# SCH_RT1064_2024-05-07.net
KiCad netlist of a schematic drawn in EasyEDA
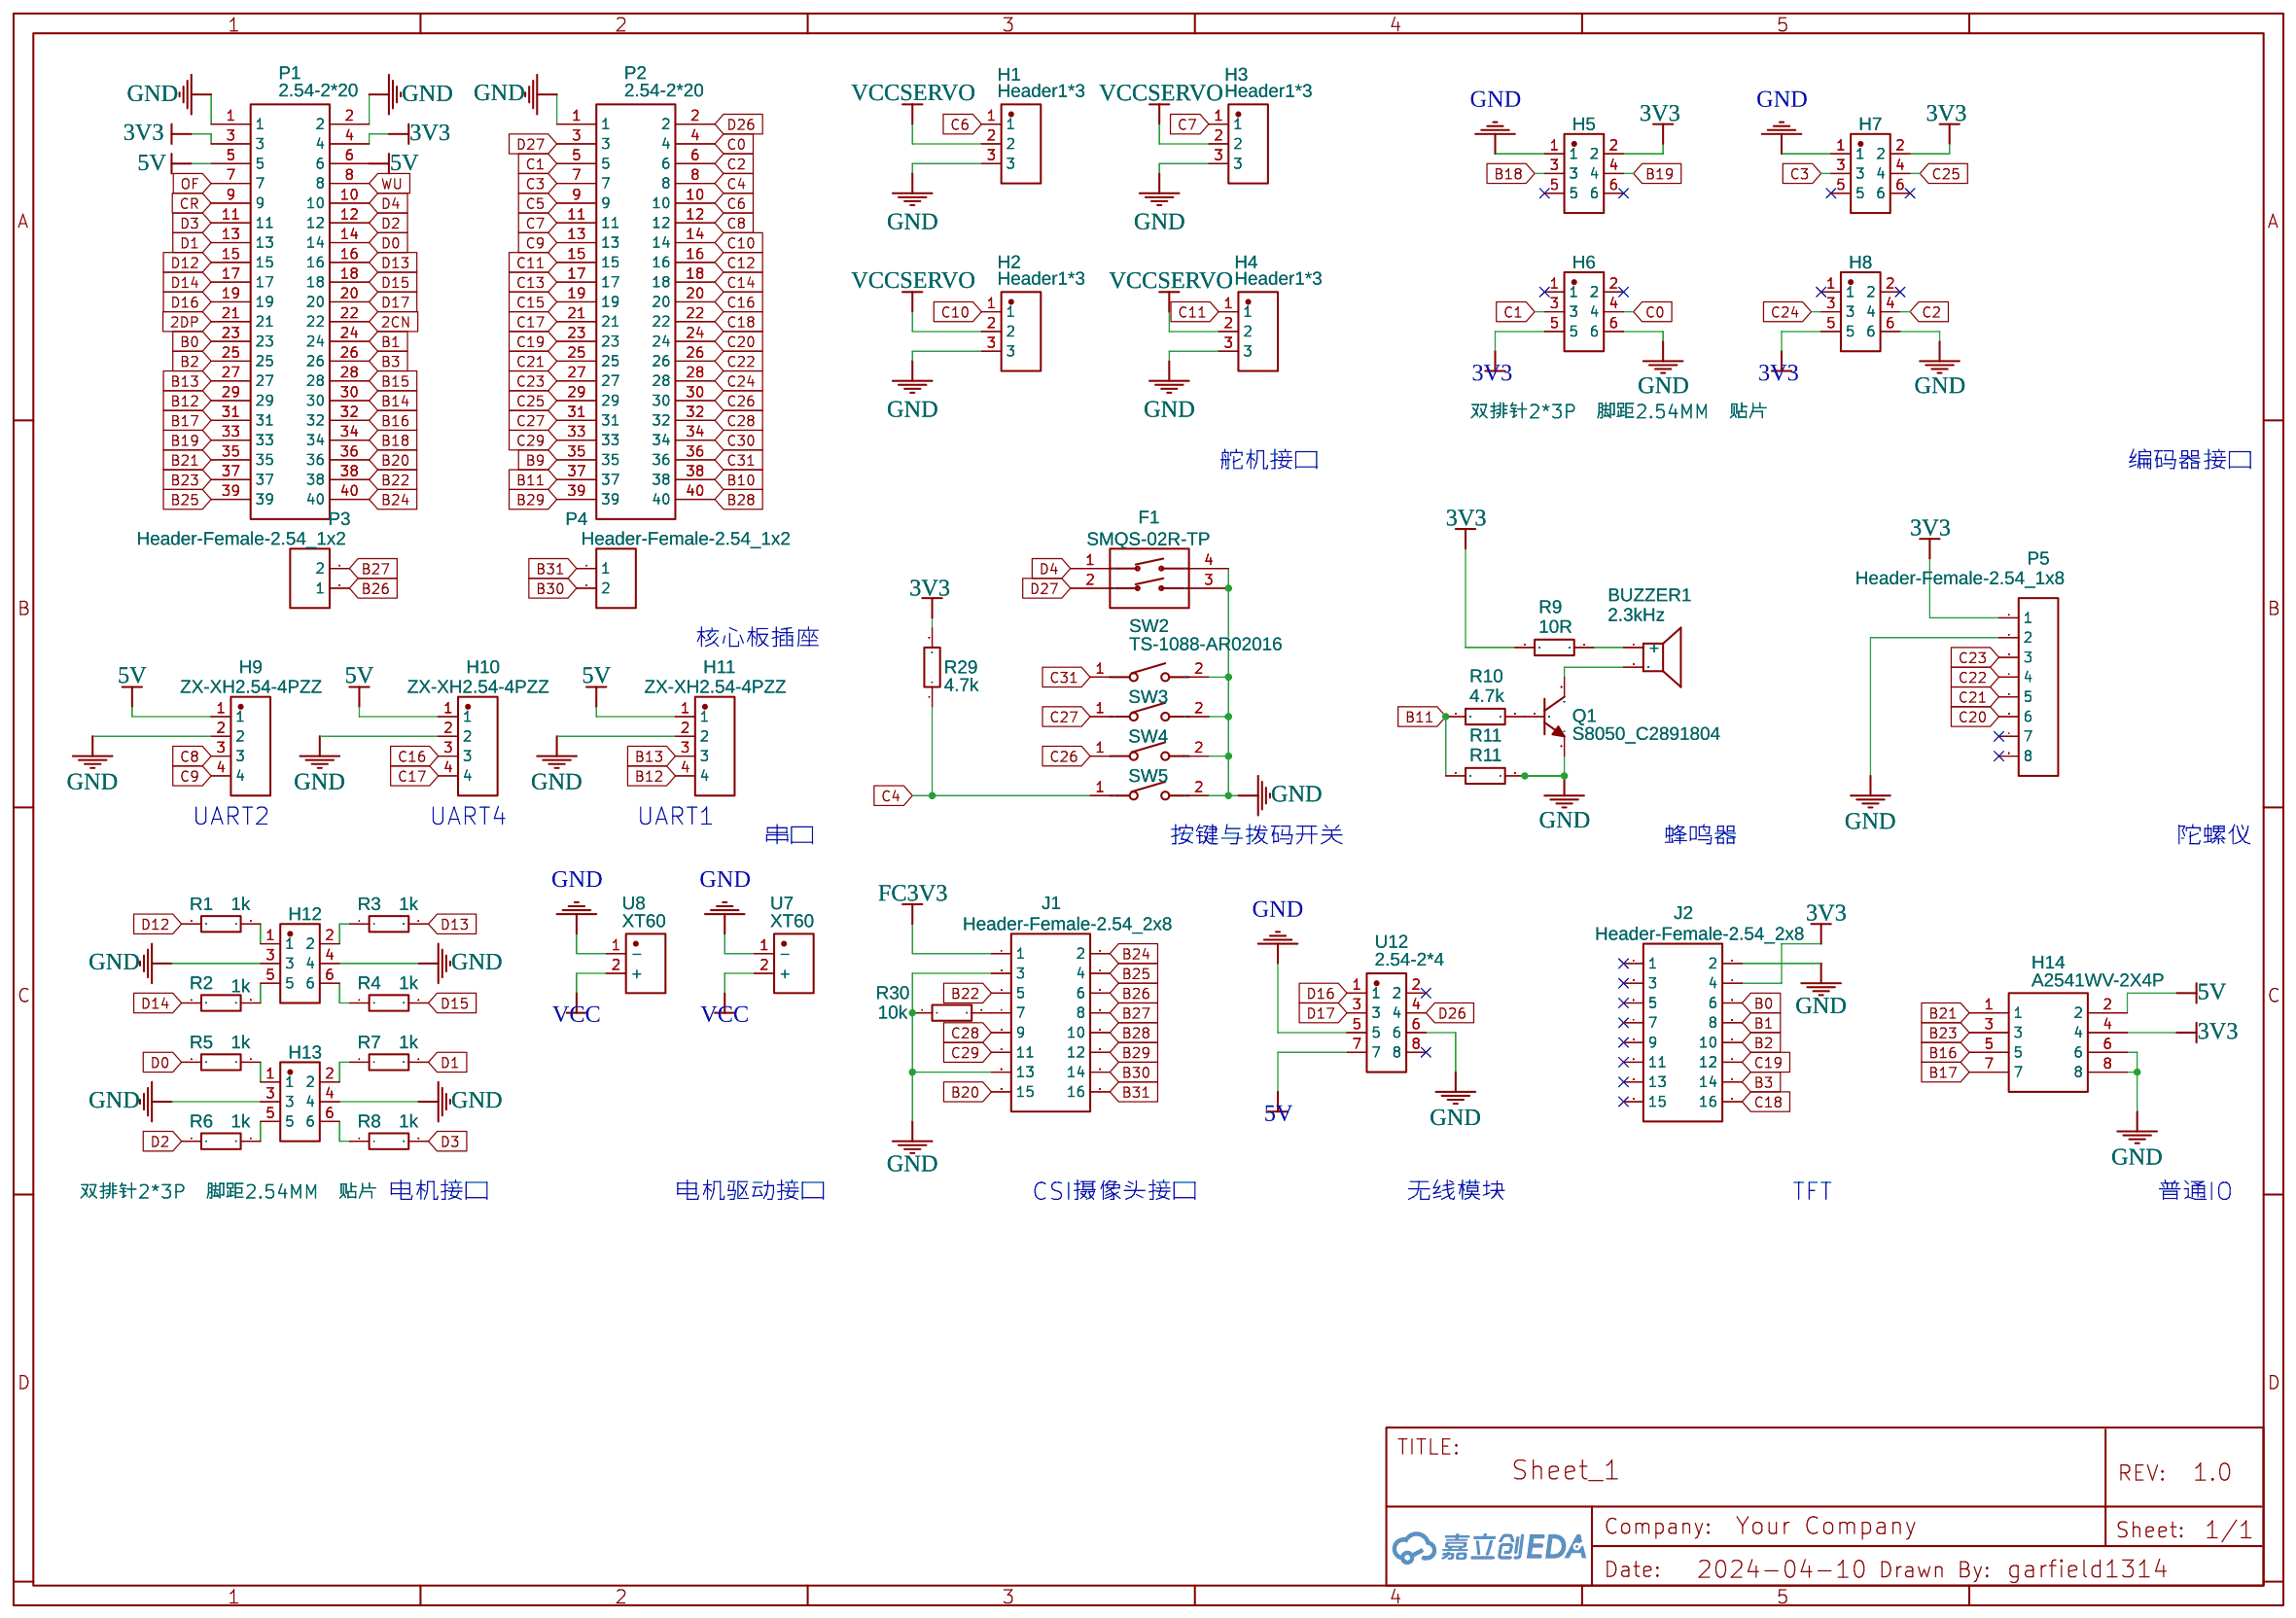
[diagram p0: Sheet_1_V2]
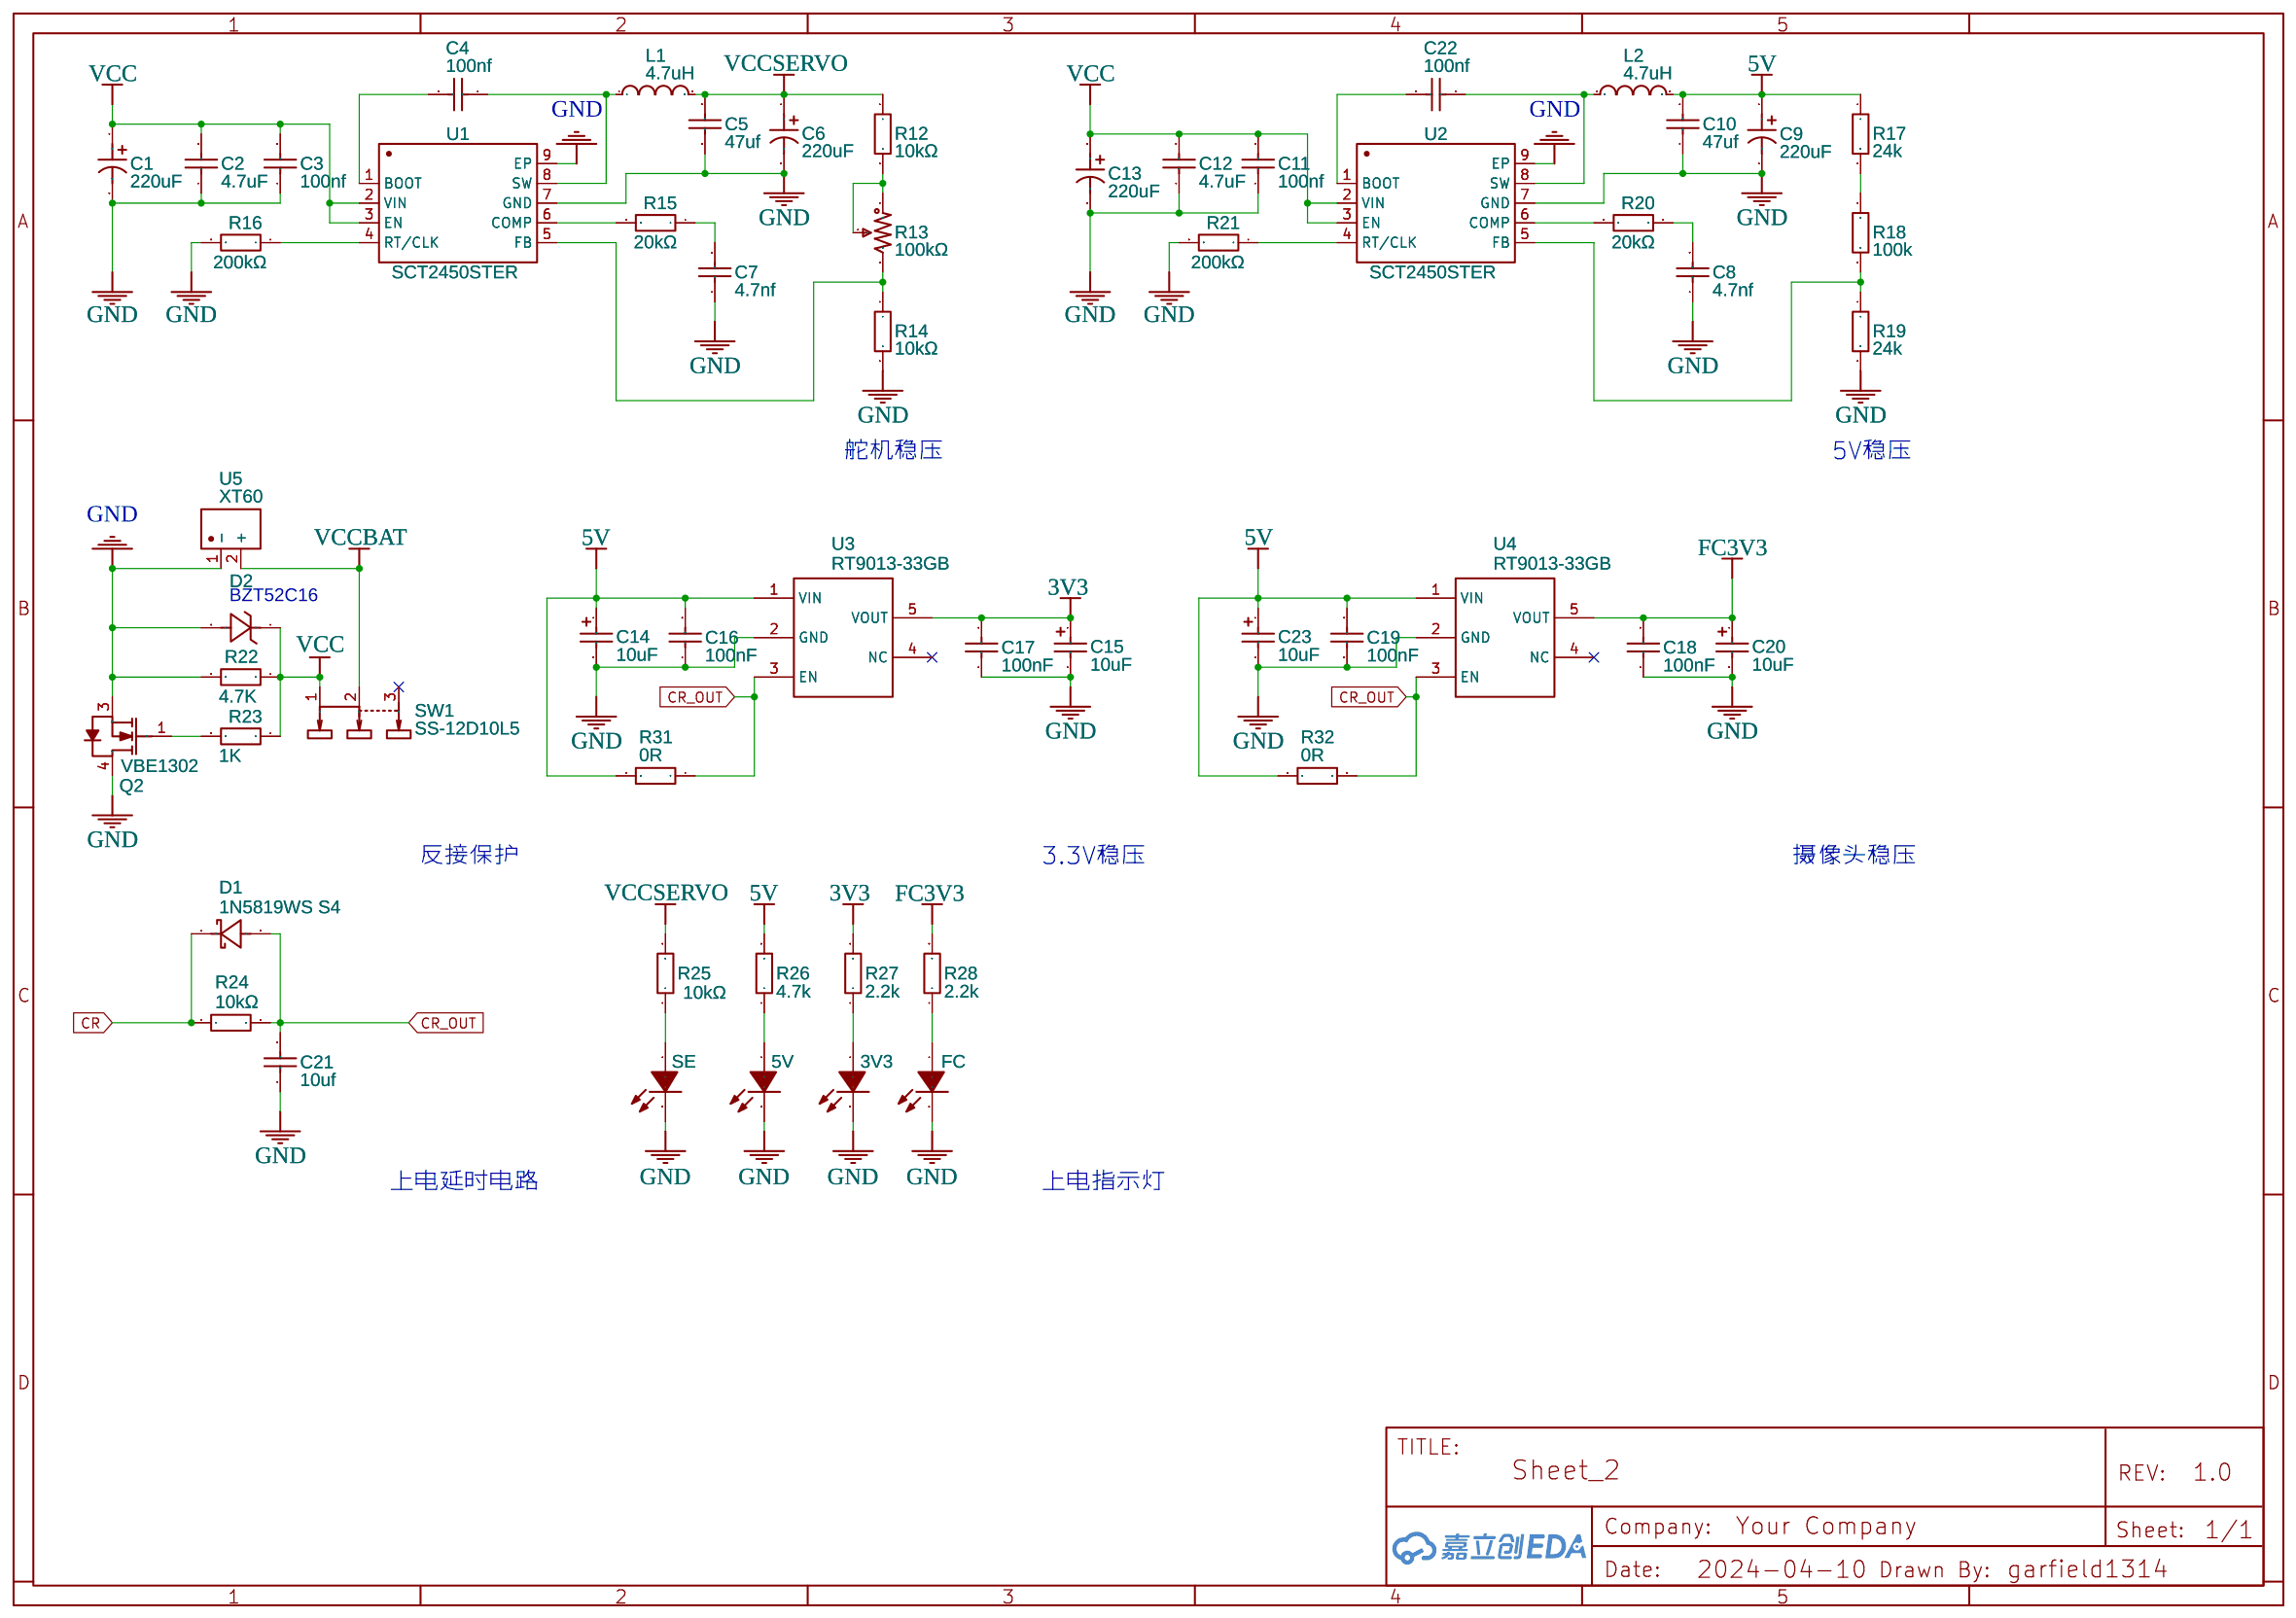
[diagram p1: Sheet_2_V2]

(export (version "E")
  (design (tool "Eeschema 10.0.6"))
  (components
    (comp (ref "BUZZER1")
      (value "2.3kHz")
      (fields (field (name "Manufacturer Part") "TMB12A05") (field (name "Manufacturer") "华能"))
      (libsource (lib "") (part "TMB12A05"))
    )
    (comp (ref "F1")
      (value "SMQS-02R-TP")
      (fields (field (name "Manufacturer") "SM Switch"))
      (libsource (lib "") (part "SMQS-02R-TP"))
    )
    (comp (ref "H1")
      (value "Header1*3")
      (fields (field (name "Manufacturer Part") "PZ254V-11-03P") (field (name "Manufacturer") "XFCN(兴飞)"))
      (libsource (lib "") (part "PZ254V-11-03P_C2937625"))
    )
    (comp (ref "H2")
      (value "Header1*3")
      (fields (field (name "Manufacturer Part") "PZ254V-11-03P") (field (name "Manufacturer") "XFCN(兴飞)"))
      (libsource (lib "") (part "PZ254V-11-03P_C2937625"))
    )
    (comp (ref "H3")
      (value "Header1*3")
      (fields (field (name "Manufacturer Part") "PZ254V-11-03P") (field (name "Manufacturer") "XFCN(兴飞)"))
      (libsource (lib "") (part "PZ254V-11-03P_C2937625"))
    )
    (comp (ref "H4")
      (value "Header1*3")
      (fields (field (name "Manufacturer Part") "PZ254V-11-03P") (field (name "Manufacturer") "XFCN(兴飞)"))
      (libsource (lib "") (part "PZ254V-11-03P_C2937625"))
    )
    (comp (ref "H5")
      (value "双排针2*3P  脚距2.54MM  贴片")
      (fields
        (field (name "Manufacturer Part") "双排针2*3P 脚距2.54mm 贴片")
        (field (name "Manufacturer") "BOOMELE(博穆精密)")
      )
      (libsource (lib "") (part "双排针2*3P  脚距2.54MM  贴片"))
    )
    (comp (ref "H6")
      (value "双排针2*3P  脚距2.54MM  贴片")
      (fields
        (field (name "Manufacturer Part") "双排针2*3P 脚距2.54mm 贴片")
        (field (name "Manufacturer") "BOOMELE(博穆精密)")
      )
      (libsource (lib "") (part "双排针2*3P  脚距2.54MM  贴片"))
    )
    (comp (ref "H7")
      (value "双排针2*3P  脚距2.54MM  贴片")
      (fields
        (field (name "Manufacturer Part") "双排针2*3P 脚距2.54mm 贴片")
        (field (name "Manufacturer") "BOOMELE(博穆精密)")
      )
      (libsource (lib "") (part "双排针2*3P  脚距2.54MM  贴片"))
    )
    (comp (ref "H8")
      (value "双排针2*3P  脚距2.54MM  贴片")
      (fields
        (field (name "Manufacturer Part") "双排针2*3P 脚距2.54mm 贴片")
        (field (name "Manufacturer") "BOOMELE(博穆精密)")
      )
      (libsource (lib "") (part "双排针2*3P  脚距2.54MM  贴片"))
    )
    (comp (ref "H9")
      (value "ZX-XH2.54-4PZZ")
      (fields (field (name "Manufacturer") "Megastar(兆星)"))
      (libsource (lib "") (part "ZX-XH2.54-4PZZ"))
    )
    (comp (ref "H10")
      (value "ZX-XH2.54-4PZZ")
      (fields (field (name "Manufacturer") "Megastar(兆星)"))
      (libsource (lib "") (part "ZX-XH2.54-4PZZ"))
    )
    (comp (ref "H11")
      (value "ZX-XH2.54-4PZZ")
      (fields (field (name "Manufacturer") "Megastar(兆星)"))
      (libsource (lib "") (part "ZX-XH2.54-4PZZ"))
    )
    (comp (ref "H12")
      (value "双排针2*3P  脚距2.54MM  贴片")
      (fields
        (field (name "Manufacturer Part") "双排针2*3P 脚距2.54mm 贴片")
        (field (name "Manufacturer") "BOOMELE(博穆精密)")
      )
      (libsource (lib "") (part "双排针2*3P  脚距2.54MM  贴片"))
    )
    (comp (ref "H13")
      (value "双排针2*3P  脚距2.54MM  贴片")
      (fields
        (field (name "Manufacturer Part") "双排针2*3P 脚距2.54mm 贴片")
        (field (name "Manufacturer") "BOOMELE(博穆精密)")
      )
      (libsource (lib "") (part "双排针2*3P  脚距2.54MM  贴片"))
    )
    (comp (ref "H14")
      (value "A2541WV-2X4P")
      (fields (field (name "Manufacturer Part") "A2541WV-2x4P") (field (name "Manufacturer") "CJT(长江连接器)"))
      (libsource (lib "") (part "A2541WV-2X4P"))
    )
    (comp (ref "J1")
      (value "Header-Female-2.54_2x8")
      (fields (field (name "Manufacturer Part") "2.54-2*8P母") (field (name "Manufacturer") "BOOMELE(博穆精密)"))
      (libsource (lib "") (part "Header-Female-2.54_2x8"))
    )
    (comp (ref "J2")
      (value "Header-Female-2.54_2x8")
      (fields (field (name "Manufacturer Part") "2.54-2*8P母") (field (name "Manufacturer") "BOOMELE(博穆精密)"))
      (libsource (lib "") (part "Header-Female-2.54_2x8"))
    )
    (comp (ref "P1")
      (value "2.54-2*20")
      (fields (field (name "Manufacturer") "ZHOURI(洲日)"))
      (libsource (lib "") (part "2.54-2*20"))
    )
    (comp (ref "P2")
      (value "2.54-2*20")
      (fields (field (name "Manufacturer") "ZHOURI(洲日)"))
      (libsource (lib "") (part "2.54-2*20"))
    )
    (comp (ref "P3")
      (value "Header-Female-2.54_1x2")
      (fields (field (name "Manufacturer Part") "2.54-1*2P母") (field (name "Manufacturer") "BOOMELE(博穆精密)"))
      (libsource (lib "") (part "Header-Female-2.54_1x2"))
    )
    (comp (ref "P4")
      (value "Header-Female-2.54_1x2")
      (fields (field (name "Manufacturer Part") "2.54-1*2P母") (field (name "Manufacturer") "BOOMELE(博穆精密)"))
      (libsource (lib "") (part "Header-Female-2.54_1x2_1"))
    )
    (comp (ref "P5")
      (value "Header-Female-2.54_1x8")
      (fields (field (name "Manufacturer Part") "2.54-1*8P母环保") (field (name "Manufacturer") "BOOMELE(博穆精密)"))
      (libsource (lib "") (part "Header-Female-2.54_1x8"))
    )
    (comp (ref "Q1")
      (value "S8050_C2891804")
      (fields (field (name "Manufacturer Part") "S8050") (field (name "Manufacturer") "YONGYUTAI(永裕泰)"))
      (libsource (lib "") (part "S8050_C2891804"))
    )
    (comp (ref "R1")
      (value "1k")
      (fields
        (field (name "Manufacturer Part") "0805W8F2003T5E")
        (field (name "Manufacturer") "UNI-ROYAL(厚声)")
      )
      (libsource (lib "") (part "0805W8F2003T5E"))
    )
    (comp (ref "R2")
      (value "1k")
      (fields
        (field (name "Manufacturer Part") "0805W8F2003T5E")
        (field (name "Manufacturer") "UNI-ROYAL(厚声)")
      )
      (libsource (lib "") (part "0805W8F2003T5E"))
    )
    (comp (ref "R3")
      (value "1k")
      (fields
        (field (name "Manufacturer Part") "0805W8F2003T5E")
        (field (name "Manufacturer") "UNI-ROYAL(厚声)")
      )
      (libsource (lib "") (part "0805W8F2003T5E"))
    )
    (comp (ref "R4")
      (value "1k")
      (fields
        (field (name "Manufacturer Part") "0805W8F2003T5E")
        (field (name "Manufacturer") "UNI-ROYAL(厚声)")
      )
      (libsource (lib "") (part "0805W8F2003T5E"))
    )
    (comp (ref "R5")
      (value "1k")
      (fields
        (field (name "Manufacturer Part") "0805W8F2003T5E")
        (field (name "Manufacturer") "UNI-ROYAL(厚声)")
      )
      (libsource (lib "") (part "0805W8F2003T5E"))
    )
    (comp (ref "R6")
      (value "1k")
      (fields
        (field (name "Manufacturer Part") "0805W8F2003T5E")
        (field (name "Manufacturer") "UNI-ROYAL(厚声)")
      )
      (libsource (lib "") (part "0805W8F2003T5E"))
    )
    (comp (ref "R7")
      (value "1k")
      (fields
        (field (name "Manufacturer Part") "0805W8F2003T5E")
        (field (name "Manufacturer") "UNI-ROYAL(厚声)")
      )
      (libsource (lib "") (part "0805W8F2003T5E"))
    )
    (comp (ref "R8")
      (value "1k")
      (fields
        (field (name "Manufacturer Part") "0805W8F2003T5E")
        (field (name "Manufacturer") "UNI-ROYAL(厚声)")
      )
      (libsource (lib "") (part "0805W8F2003T5E"))
    )
    (comp (ref "R9")
      (value "10R")
      (fields
        (field (name "Manufacturer Part") "0805W8F2003T5E")
        (field (name "Manufacturer") "UNI-ROYAL(厚声)")
      )
      (libsource (lib "") (part "0805W8F2003T5E"))
    )
    (comp (ref "R10")
      (value "4.7k")
      (fields
        (field (name "Manufacturer Part") "0805W8F2003T5E")
        (field (name "Manufacturer") "UNI-ROYAL(厚声)")
      )
      (libsource (lib "") (part "0805W8F2003T5E"))
    )
    (comp (ref "R11")
      (value "R11")
      (fields
        (field (name "Manufacturer Part") "0805W8F2003T5E")
        (field (name "Manufacturer") "UNI-ROYAL(厚声)")
      )
      (libsource (lib "") (part "0805W8F2003T5E"))
    )
    (comp (ref "R29")
      (value "4.7k")
      (fields
        (field (name "Manufacturer Part") "0805W8F2003T5E")
        (field (name "Manufacturer") "UNI-ROYAL(厚声)")
      )
      (libsource (lib "") (part "0805W8F2003T5E_1"))
    )
    (comp (ref "R30")
      (value "10k")
      (fields
        (field (name "Manufacturer Part") "0805W8F2003T5E")
        (field (name "Manufacturer") "UNI-ROYAL(厚声)")
      )
      (libsource (lib "") (part "0805W8F2003T5E"))
    )
    (comp (ref "SW2")
      (value "TS-1088-AR02016")
      (fields (field (name "Manufacturer") "XUNPU(讯普)"))
      (libsource (lib "") (part "TS-1088-AR02016"))
    )
    (comp (ref "SW3")
      (value "TS-1088-AR02016")
      (fields (field (name "Manufacturer") "XUNPU(讯普)"))
      (libsource (lib "") (part "TS-1088-AR02016"))
    )
    (comp (ref "SW4")
      (value "TS-1088-AR02016")
      (fields (field (name "Manufacturer") "XUNPU(讯普)"))
      (libsource (lib "") (part "TS-1088-AR02016"))
    )
    (comp (ref "SW5")
      (value "TS-1088-AR02016")
      (fields (field (name "Manufacturer") "XUNPU(讯普)"))
      (libsource (lib "") (part "TS-1088-AR02016"))
    )
    (comp (ref "U7")
      (value "XT60")
      (fields (field (name "Manufacturer") "AMASS(艾迈斯)"))
      (libsource (lib "") (part "XT60"))
    )
    (comp (ref "U8")
      (value "XT60")
      (fields (field (name "Manufacturer") "AMASS(艾迈斯)"))
      (libsource (lib "") (part "XT60"))
    )
    (comp (ref "U12")
      (value "2.54-2*4")
      (fields (field (name "Manufacturer") "ZHOURI(洲日)"))
      (libsource (lib "") (part "2.54-2*4"))
    )
    (comp (ref "3V3")
      (value "FC-2012HRK-620D")
      (fields (field (name "Manufacturer Part") "NCD0805R1") (field (name "Manufacturer") "国星光电"))
      (libsource (lib "") (part "FC-2012HRK-620D_2"))
    )
    (comp (ref "5V")
      (value "FC-2012HRK-620D")
      (fields (field (name "Manufacturer Part") "NCD0805R1") (field (name "Manufacturer") "国星光电"))
      (libsource (lib "") (part "FC-2012HRK-620D_3"))
    )
    (comp (ref "C1")
      (value "220uF")
      (fields
        (field (name "Manufacturer Part") "RVE100UF35V67RV0072")
        (field (name "Manufacturer") "KNSCHA(科尼盛)")
      )
      (libsource (lib "") (part "RVE100UF35V67RV0072"))
    )
    (comp (ref "C2")
      (value "4.7uF")
      (fields
        (field (name "Manufacturer Part") "CL21A475KAQNNNE")
        (field (name "Manufacturer") "SAMSUNG(三星)")
      )
      (libsource (lib "") (part "CL21A475KAQNNNE"))
    )
    (comp (ref "C3")
      (value "100nf")
      (fields
        (field (name "Manufacturer Part") "CL21A475KAQNNNE")
        (field (name "Manufacturer") "SAMSUNG(三星)")
      )
      (libsource (lib "") (part "CL21A475KAQNNNE"))
    )
    (comp (ref "C4")
      (value "100nf")
      (fields
        (field (name "Manufacturer Part") "CL21A475KAQNNNE")
        (field (name "Manufacturer") "SAMSUNG(三星)")
      )
      (libsource (lib "") (part "CL21A475KAQNNNE_1"))
    )
    (comp (ref "C5")
      (value "47uf")
      (fields
        (field (name "Manufacturer Part") "CL21A475KAQNNNE")
        (field (name "Manufacturer") "SAMSUNG(三星)")
      )
      (libsource (lib "") (part "CL21A475KAQNNNE"))
    )
    (comp (ref "C6")
      (value "220uF")
      (fields
        (field (name "Manufacturer Part") "RVE100UF35V67RV0072")
        (field (name "Manufacturer") "KNSCHA(科尼盛)")
      )
      (libsource (lib "") (part "RVE100UF35V67RV0072"))
    )
    (comp (ref "C7")
      (value "4.7nf")
      (fields
        (field (name "Manufacturer Part") "CL21A475KAQNNNE")
        (field (name "Manufacturer") "SAMSUNG(三星)")
      )
      (libsource (lib "") (part "CL21A475KAQNNNE"))
    )
    (comp (ref "C8")
      (value "4.7nf")
      (fields
        (field (name "Manufacturer Part") "CL21A475KAQNNNE")
        (field (name "Manufacturer") "SAMSUNG(三星)")
      )
      (libsource (lib "") (part "CL21A475KAQNNNE"))
    )
    (comp (ref "C9")
      (value "220uF")
      (fields
        (field (name "Manufacturer Part") "RVE100UF35V67RV0072")
        (field (name "Manufacturer") "KNSCHA(科尼盛)")
      )
      (libsource (lib "") (part "RVE100UF35V67RV0072"))
    )
    (comp (ref "C10")
      (value "47uf")
      (fields
        (field (name "Manufacturer Part") "CL21A475KAQNNNE")
        (field (name "Manufacturer") "SAMSUNG(三星)")
      )
      (libsource (lib "") (part "CL21A475KAQNNNE"))
    )
    (comp (ref "C11")
      (value "100nf")
      (fields
        (field (name "Manufacturer Part") "CL21A475KAQNNNE")
        (field (name "Manufacturer") "SAMSUNG(三星)")
      )
      (libsource (lib "") (part "CL21A475KAQNNNE"))
    )
    (comp (ref "C12")
      (value "4.7uF")
      (fields
        (field (name "Manufacturer Part") "CL21A475KAQNNNE")
        (field (name "Manufacturer") "SAMSUNG(三星)")
      )
      (libsource (lib "") (part "CL21A475KAQNNNE"))
    )
    (comp (ref "C13")
      (value "220uF")
      (fields
        (field (name "Manufacturer Part") "RVE100UF35V67RV0072")
        (field (name "Manufacturer") "KNSCHA(科尼盛)")
      )
      (libsource (lib "") (part "RVE100UF35V67RV0072"))
    )
    (comp (ref "C14")
      (value "10uF")
      (fields (field (name "Manufacturer Part") "TAJA106K016RNJ") (field (name "Manufacturer") "Kyocera AVX"))
      (libsource (lib "") (part "TAJA106K016RNJ"))
    )
    (comp (ref "C15")
      (value "10uF")
      (fields (field (name "Manufacturer Part") "TAJA106K016RNJ") (field (name "Manufacturer") "Kyocera AVX"))
      (libsource (lib "") (part "TAJA106K016RNJ"))
    )
    (comp (ref "C16")
      (value "100nF")
      (fields
        (field (name "Manufacturer Part") "CL21A475KAQNNNE")
        (field (name "Manufacturer") "SAMSUNG(三星)")
      )
      (libsource (lib "") (part "CL21A475KAQNNNE"))
    )
    (comp (ref "C17")
      (value "100nF")
      (fields
        (field (name "Manufacturer Part") "CL21A475KAQNNNE")
        (field (name "Manufacturer") "SAMSUNG(三星)")
      )
      (libsource (lib "") (part "CL21A475KAQNNNE"))
    )
    (comp (ref "C18")
      (value "100nF")
      (fields
        (field (name "Manufacturer Part") "CL21A475KAQNNNE")
        (field (name "Manufacturer") "SAMSUNG(三星)")
      )
      (libsource (lib "") (part "CL21A475KAQNNNE"))
    )
    (comp (ref "C19")
      (value "100nF")
      (fields
        (field (name "Manufacturer Part") "CL21A475KAQNNNE")
        (field (name "Manufacturer") "SAMSUNG(三星)")
      )
      (libsource (lib "") (part "CL21A475KAQNNNE"))
    )
    (comp (ref "C20")
      (value "10uF")
      (fields (field (name "Manufacturer Part") "TAJA106K016RNJ") (field (name "Manufacturer") "Kyocera AVX"))
      (libsource (lib "") (part "TAJA106K016RNJ"))
    )
    (comp (ref "C21")
      (value "10uf")
      (fields
        (field (name "Manufacturer Part") "CL21A475KAQNNNE")
        (field (name "Manufacturer") "SAMSUNG(三星)")
      )
      (libsource (lib "") (part "CL21A475KAQNNNE"))
    )
    (comp (ref "C22")
      (value "100nf")
      (fields
        (field (name "Manufacturer Part") "CL21A475KAQNNNE")
        (field (name "Manufacturer") "SAMSUNG(三星)")
      )
      (libsource (lib "") (part "CL21A475KAQNNNE_1"))
    )
    (comp (ref "C23")
      (value "10uF")
      (fields (field (name "Manufacturer Part") "TAJA106K016RNJ") (field (name "Manufacturer") "Kyocera AVX"))
      (libsource (lib "") (part "TAJA106K016RNJ"))
    )
    (comp (ref "D1")
      (value "1N5819WS S4")
      (fields (field (name "Manufacturer") "JSMSEMI(杰盛微)"))
      (libsource (lib "") (part "1N5819WS S4"))
    )
    (comp (ref "D2")
      (value "D2")
      (fields (field (name "Manufacturer Part") "BZT52C16") (field (name "Manufacturer") "TWGMC(台湾迪嘉)"))
      (libsource (lib "") (part "BZT52C16_C727007"))
    )
    (comp (ref "FC")
      (value "FC-2012HRK-620D")
      (fields (field (name "Manufacturer Part") "NCD0805R1") (field (name "Manufacturer") "国星光电"))
      (libsource (lib "") (part "FC-2012HRK-620D"))
    )
    (comp (ref "L1")
      (value "4.7uH")
      (fields
        (field (name "Manufacturer Part") "SLO0530H4R7MTT")
        (field (name "Manufacturer") "Sunltech(韩国顺磁)")
      )
      (libsource (lib "") (part "SLO0530H4R7MTT"))
    )
    (comp (ref "L2")
      (value "4.7uH")
      (fields
        (field (name "Manufacturer Part") "SLO0530H4R7MTT")
        (field (name "Manufacturer") "Sunltech(韩国顺磁)")
      )
      (libsource (lib "") (part "SLO0530H4R7MTT_1"))
    )
    (comp (ref "Q2")
      (value "VBE1302")
      (fields (field (name "Manufacturer") "VBsemi(微碧半导体)"))
      (libsource (lib "") (part "VBE1302"))
    )
    (comp (ref "R12")
      (value "10kΩ")
      (fields
        (field (name "Manufacturer Part") "0805W8F2003T5E")
        (field (name "Manufacturer") "UNI-ROYAL(厚声)")
      )
      (libsource (lib "") (part "0805W8F2003T5E_3"))
    )
    (comp (ref "R13")
      (value "100kΩ")
      (fields (field (name "Manufacturer Part") "3296W-1-103") (field (name "Manufacturer") "BOCHEN(博晨)"))
      (libsource (lib "") (part "3296W-1-103"))
    )
    (comp (ref "R14")
      (value "10kΩ")
      (fields
        (field (name "Manufacturer Part") "0805W8F2003T5E")
        (field (name "Manufacturer") "UNI-ROYAL(厚声)")
      )
      (libsource (lib "") (part "0805W8F2003T5E_3"))
    )
    (comp (ref "R15")
      (value "20kΩ")
      (fields
        (field (name "Manufacturer Part") "0805W8F2003T5E")
        (field (name "Manufacturer") "UNI-ROYAL(厚声)")
      )
      (libsource (lib "") (part "0805W8F2003T5E_1"))
    )
    (comp (ref "R16")
      (value "200kΩ")
      (fields
        (field (name "Manufacturer Part") "0805W8F2003T5E")
        (field (name "Manufacturer") "UNI-ROYAL(厚声)")
      )
      (libsource (lib "") (part "0805W8F2003T5E_1"))
    )
    (comp (ref "R17")
      (value "24k")
      (fields
        (field (name "Manufacturer Part") "0805W8F2003T5E")
        (field (name "Manufacturer") "UNI-ROYAL(厚声)")
      )
      (libsource (lib "") (part "0805W8F2003T5E_3"))
    )
    (comp (ref "R18")
      (value "100k")
      (fields
        (field (name "Manufacturer Part") "0805W8F2003T5E")
        (field (name "Manufacturer") "UNI-ROYAL(厚声)")
      )
      (libsource (lib "") (part "0805W8F2003T5E_3"))
    )
    (comp (ref "R19")
      (value "24k")
      (fields
        (field (name "Manufacturer Part") "0805W8F2003T5E")
        (field (name "Manufacturer") "UNI-ROYAL(厚声)")
      )
      (libsource (lib "") (part "0805W8F2003T5E_3"))
    )
    (comp (ref "R20")
      (value "20kΩ")
      (fields
        (field (name "Manufacturer Part") "0805W8F2003T5E")
        (field (name "Manufacturer") "UNI-ROYAL(厚声)")
      )
      (libsource (lib "") (part "0805W8F2003T5E_1"))
    )
    (comp (ref "R21")
      (value "200kΩ")
      (fields
        (field (name "Manufacturer Part") "0805W8F2003T5E")
        (field (name "Manufacturer") "UNI-ROYAL(厚声)")
      )
      (libsource (lib "") (part "0805W8F2003T5E_1"))
    )
    (comp (ref "R22")
      (value "4.7K")
      (fields
        (field (name "Manufacturer Part") "0805W8F2003T5E")
        (field (name "Manufacturer") "UNI-ROYAL(厚声)")
      )
      (libsource (lib "") (part "0805W8F2003T5E_1"))
    )
    (comp (ref "R23")
      (value "1K")
      (fields
        (field (name "Manufacturer Part") "0805W8F2003T5E")
        (field (name "Manufacturer") "UNI-ROYAL(厚声)")
      )
      (libsource (lib "") (part "0805W8F2003T5E_1"))
    )
    (comp (ref "R24")
      (value "10kΩ")
      (fields
        (field (name "Manufacturer Part") "0805W8F2003T5E")
        (field (name "Manufacturer") "UNI-ROYAL(厚声)")
      )
      (libsource (lib "") (part "0805W8F2003T5E"))
    )
    (comp (ref "R25")
      (value "10kΩ")
      (fields
        (field (name "Manufacturer Part") "0805W8F2003T5E")
        (field (name "Manufacturer") "UNI-ROYAL(厚声)")
      )
      (libsource (lib "") (part "0805W8F2003T5E_2"))
    )
    (comp (ref "R26")
      (value "4.7k")
      (fields
        (field (name "Manufacturer Part") "0805W8F2003T5E")
        (field (name "Manufacturer") "UNI-ROYAL(厚声)")
      )
      (libsource (lib "") (part "0805W8F2003T5E_2"))
    )
    (comp (ref "R27")
      (value "2.2k")
      (fields
        (field (name "Manufacturer Part") "0805W8F2003T5E")
        (field (name "Manufacturer") "UNI-ROYAL(厚声)")
      )
      (libsource (lib "") (part "0805W8F2003T5E_2"))
    )
    (comp (ref "R28")
      (value "2.2k")
      (fields
        (field (name "Manufacturer Part") "0805W8F2003T5E")
        (field (name "Manufacturer") "UNI-ROYAL(厚声)")
      )
      (libsource (lib "") (part "0805W8F2003T5E_2"))
    )
    (comp (ref "R31")
      (value "0R")
      (fields
        (field (name "Manufacturer Part") "0805W8F2003T5E")
        (field (name "Manufacturer") "UNI-ROYAL(厚声)")
      )
      (libsource (lib "") (part "0805W8F2003T5E_1"))
    )
    (comp (ref "R32")
      (value "0R")
      (fields
        (field (name "Manufacturer Part") "0805W8F2003T5E")
        (field (name "Manufacturer") "UNI-ROYAL(厚声)")
      )
      (libsource (lib "") (part "0805W8F2003T5E_1"))
    )
    (comp (ref "SE")
      (value "FC-2012HRK-620D")
      (fields (field (name "Manufacturer Part") "NCD0805R1") (field (name "Manufacturer") "国星光电"))
      (libsource (lib "") (part "FC-2012HRK-620D_1"))
    )
    (comp (ref "SW1")
      (value "SS-12D10L5")
      (fields (field (name "Manufacturer") "XKB Connectivity(中国星坤)"))
      (libsource (lib "") (part "SS-12D10L5"))
    )
    (comp (ref "U1")
      (value "SCT2450STER")
      (fields (field (name "Manufacturer") "SCT(芯洲科技)"))
      (libsource (lib "") (part "SCT2450STER"))
    )
    (comp (ref "U2")
      (value "SCT2450STER")
      (fields (field (name "Manufacturer") "SCT(芯洲科技)"))
      (libsource (lib "") (part "SCT2450STER"))
    )
    (comp (ref "U3")
      (value "RT9013-33GB")
      (fields (field (name "Manufacturer") "RICHTEK(立锜)"))
      (libsource (lib "") (part "RT9013-33GB"))
    )
    (comp (ref "U4")
      (value "RT9013-33GB")
      (fields (field (name "Manufacturer") "RICHTEK(立锜)"))
      (libsource (lib "") (part "RT9013-33GB"))
    )
    (comp (ref "U5")
      (value "XT60")
      (fields (field (name "Manufacturer") "AMASS(艾迈斯)"))
      (libsource (lib "") (part "XT60"))
    )
  )
  (nets
    (net (code "1") (name "2CN") (class "Default")
      (node (ref "P1") (pin "22") (pinfunction "22_22") (pintype "unspecified"))
    )
    (net (code "2") (name "2DP") (class "Default")
      (node (ref "P1") (pin "21") (pinfunction "21_21") (pintype "unspecified"))
    )
    (net (code "3") (name "3V3") (class "Default")
      (node (ref "C15") (pin "1") (pinfunction "1_1") (pintype "input"))
      (node (ref "C17") (pin "2") (pinfunction "2_2") (pintype "input"))
      (node (ref "H14") (pin "4") (pinfunction "4_4") (pintype "unspecified"))
      (node (ref "H5") (pin "2") (pinfunction "2_2") (pintype "unspecified"))
      (node (ref "H6") (pin "5") (pinfunction "5_5") (pintype "unspecified"))
      (node (ref "H7") (pin "2") (pinfunction "2_2") (pintype "unspecified"))
      (node (ref "H8") (pin "5") (pinfunction "5_5") (pintype "unspecified"))
      (node (ref "J2") (pin "4") (pinfunction "4_4") (pintype "input"))
      (node (ref "P1") (pin "3") (pinfunction "3_3") (pintype "unspecified"))
      (node (ref "P1") (pin "4") (pinfunction "4_4") (pintype "unspecified"))
      (node (ref "P5") (pin "1") (pinfunction "1_1") (pintype "input"))
      (node (ref "R27") (pin "2") (pinfunction "2_2") (pintype "input"))
      (node (ref "R29") (pin "2") (pinfunction "2_2") (pintype "input"))
      (node (ref "R9") (pin "1") (pinfunction "1_1") (pintype "input"))
      (node (ref "U3") (pin "5") (pinfunction "VOUT_5") (pintype "unspecified"))
    )
    (net (code "4") (name "5V") (class "Default")
      (node (ref "C10") (pin "2") (pinfunction "2_2") (pintype "input"))
      (node (ref "C14") (pin "1") (pinfunction "1_1") (pintype "input"))
      (node (ref "C16") (pin "2") (pinfunction "2_2") (pintype "input"))
      (node (ref "C19") (pin "2") (pinfunction "2_2") (pintype "input"))
      (node (ref "C23") (pin "1") (pinfunction "1_1") (pintype "input"))
      (node (ref "C9") (pin "1") (pinfunction "1_1") (pintype "input"))
      (node (ref "H10") (pin "1") (pinfunction "1_1") (pintype "unspecified"))
      (node (ref "H11") (pin "1") (pinfunction "1_1") (pintype "unspecified"))
      (node (ref "H14") (pin "2") (pinfunction "2_2") (pintype "unspecified"))
      (node (ref "H9") (pin "1") (pinfunction "1_1") (pintype "unspecified"))
      (node (ref "L2") (pin "2") (pinfunction "2_2") (pintype "unspecified"))
      (node (ref "P1") (pin "5") (pinfunction "5_5") (pintype "unspecified"))
      (node (ref "P1") (pin "6") (pinfunction "6_6") (pintype "unspecified"))
      (node (ref "R17") (pin "1") (pinfunction "1_1") (pintype "input"))
      (node (ref "R26") (pin "2") (pinfunction "2_2") (pintype "input"))
      (node (ref "R31") (pin "2") (pinfunction "2_2") (pintype "input"))
      (node (ref "R32") (pin "2") (pinfunction "2_2") (pintype "input"))
      (node (ref "U12") (pin "7") (pinfunction "7_7") (pintype "unspecified"))
      (node (ref "U3") (pin "1") (pinfunction "VIN_1") (pintype "unspecified"))
      (node (ref "U4") (pin "1") (pinfunction "VIN_1") (pintype "unspecified"))
    )
    (net (code "5") (name "B0") (class "Default")
      (node (ref "J2") (pin "6") (pinfunction "6_6") (pintype "input"))
      (node (ref "P1") (pin "23") (pinfunction "23_23") (pintype "unspecified"))
    )
    (net (code "6") (name "B1") (class "Default")
      (node (ref "J2") (pin "8") (pinfunction "8_8") (pintype "input"))
      (node (ref "P1") (pin "24") (pinfunction "24_24") (pintype "unspecified"))
    )
    (net (code "7") (name "B2") (class "Default")
      (node (ref "J2") (pin "10") (pinfunction "10_10") (pintype "input"))
      (node (ref "P1") (pin "25") (pinfunction "25_25") (pintype "unspecified"))
    )
    (net (code "8") (name "B3") (class "Default")
      (node (ref "J2") (pin "14") (pinfunction "14_14") (pintype "input"))
      (node (ref "P1") (pin "26") (pinfunction "26_26") (pintype "unspecified"))
    )
    (net (code "9") (name "B9") (class "Default")
      (node (ref "P2") (pin "35") (pinfunction "35_35") (pintype "unspecified"))
    )
    (net (code "10") (name "B10") (class "Default")
      (node (ref "P2") (pin "38") (pinfunction "38_38") (pintype "unspecified"))
    )
    (net (code "11") (name "B11") (class "Default")
      (node (ref "P2") (pin "37") (pinfunction "37_37") (pintype "unspecified"))
      (node (ref "R10") (pin "1") (pinfunction "1_1") (pintype "input"))
      (node (ref "R11") (pin "1") (pinfunction "1_1") (pintype "input"))
    )
    (net (code "12") (name "B12") (class "Default")
      (node (ref "H11") (pin "4") (pinfunction "4_4") (pintype "unspecified"))
      (node (ref "P1") (pin "29") (pinfunction "29_29") (pintype "unspecified"))
    )
    (net (code "13") (name "B13") (class "Default")
      (node (ref "H11") (pin "3") (pinfunction "3_3") (pintype "unspecified"))
      (node (ref "P1") (pin "27") (pinfunction "27_27") (pintype "unspecified"))
    )
    (net (code "14") (name "B14") (class "Default")
      (node (ref "P1") (pin "30") (pinfunction "30_30") (pintype "unspecified"))
    )
    (net (code "15") (name "B15") (class "Default")
      (node (ref "P1") (pin "28") (pinfunction "28_28") (pintype "unspecified"))
    )
    (net (code "16") (name "B16") (class "Default")
      (node (ref "H14") (pin "5") (pinfunction "5_5") (pintype "unspecified"))
      (node (ref "P1") (pin "32") (pinfunction "32_32") (pintype "unspecified"))
    )
    (net (code "17") (name "B17") (class "Default")
      (node (ref "H14") (pin "7") (pinfunction "7_7") (pintype "unspecified"))
      (node (ref "P1") (pin "31") (pinfunction "31_31") (pintype "unspecified"))
    )
    (net (code "18") (name "B18") (class "Default")
      (node (ref "H5") (pin "3") (pinfunction "3_3") (pintype "unspecified"))
      (node (ref "P1") (pin "34") (pinfunction "34_34") (pintype "unspecified"))
    )
    (net (code "19") (name "B19") (class "Default")
      (node (ref "H5") (pin "4") (pinfunction "4_4") (pintype "unspecified"))
      (node (ref "P1") (pin "33") (pinfunction "33_33") (pintype "unspecified"))
    )
    (net (code "20") (name "B20") (class "Default")
      (node (ref "J1") (pin "15") (pinfunction "15_15") (pintype "input"))
      (node (ref "P1") (pin "36") (pinfunction "36_36") (pintype "unspecified"))
    )
    (net (code "21") (name "B21") (class "Default")
      (node (ref "H14") (pin "1") (pinfunction "1_1") (pintype "unspecified"))
      (node (ref "P1") (pin "35") (pinfunction "35_35") (pintype "unspecified"))
    )
    (net (code "22") (name "B22") (class "Default")
      (node (ref "J1") (pin "5") (pinfunction "5_5") (pintype "input"))
      (node (ref "P1") (pin "38") (pinfunction "38_38") (pintype "unspecified"))
    )
    (net (code "23") (name "B23") (class "Default")
      (node (ref "H14") (pin "3") (pinfunction "3_3") (pintype "unspecified"))
      (node (ref "P1") (pin "37") (pinfunction "37_37") (pintype "unspecified"))
    )
    (net (code "24") (name "B24") (class "Default")
      (node (ref "J1") (pin "2") (pinfunction "2_2") (pintype "input"))
      (node (ref "P1") (pin "40") (pinfunction "40_40") (pintype "unspecified"))
    )
    (net (code "25") (name "B25") (class "Default")
      (node (ref "J1") (pin "4") (pinfunction "4_4") (pintype "input"))
      (node (ref "P1") (pin "39") (pinfunction "39_39") (pintype "unspecified"))
    )
    (net (code "26") (name "B26") (class "Default")
      (node (ref "J1") (pin "6") (pinfunction "6_6") (pintype "input"))
      (node (ref "P3") (pin "1") (pinfunction "1_1") (pintype "input"))
    )
    (net (code "27") (name "B27") (class "Default")
      (node (ref "J1") (pin "8") (pinfunction "8_8") (pintype "input"))
      (node (ref "P3") (pin "2") (pinfunction "2_2") (pintype "input"))
    )
    (net (code "28") (name "B28") (class "Default")
      (node (ref "J1") (pin "10") (pinfunction "10_10") (pintype "input"))
      (node (ref "P2") (pin "40") (pinfunction "40_40") (pintype "unspecified"))
    )
    (net (code "29") (name "B29") (class "Default")
      (node (ref "J1") (pin "12") (pinfunction "12_12") (pintype "input"))
      (node (ref "P2") (pin "39") (pinfunction "39_39") (pintype "unspecified"))
    )
    (net (code "30") (name "B30") (class "Default")
      (node (ref "J1") (pin "14") (pinfunction "14_14") (pintype "input"))
      (node (ref "P4") (pin "2") (pinfunction "2_2") (pintype "input"))
    )
    (net (code "31") (name "B31") (class "Default")
      (node (ref "J1") (pin "16") (pinfunction "16_16") (pintype "input"))
      (node (ref "P4") (pin "1") (pinfunction "1_1") (pintype "input"))
    )
    (net (code "32") (name "C0") (class "Default")
      (node (ref "H6") (pin "4") (pinfunction "4_4") (pintype "unspecified"))
      (node (ref "P2") (pin "4") (pinfunction "4_4") (pintype "unspecified"))
    )
    (net (code "33") (name "C1") (class "Default")
      (node (ref "H6") (pin "3") (pinfunction "3_3") (pintype "unspecified"))
      (node (ref "P2") (pin "5") (pinfunction "5_5") (pintype "unspecified"))
    )
    (net (code "34") (name "C2") (class "Default")
      (node (ref "H8") (pin "4") (pinfunction "4_4") (pintype "unspecified"))
      (node (ref "P2") (pin "6") (pinfunction "6_6") (pintype "unspecified"))
    )
    (net (code "35") (name "C3") (class "Default")
      (node (ref "H7") (pin "3") (pinfunction "3_3") (pintype "unspecified"))
      (node (ref "P2") (pin "7") (pinfunction "7_7") (pintype "unspecified"))
    )
    (net (code "36") (name "C4") (class "Default")
      (node (ref "P2") (pin "8") (pinfunction "8_8") (pintype "unspecified"))
      (node (ref "R29") (pin "1") (pinfunction "1_1") (pintype "input"))
      (node (ref "SW5") (pin "1") (pinfunction "1_1") (pintype "unspecified"))
    )
    (net (code "37") (name "C5") (class "Default")
      (node (ref "P2") (pin "9") (pinfunction "9_9") (pintype "unspecified"))
    )
    (net (code "38") (name "C6") (class "Default")
      (node (ref "H1") (pin "1") (pinfunction "1_1") (pintype "unspecified"))
      (node (ref "P2") (pin "10") (pinfunction "10_10") (pintype "unspecified"))
    )
    (net (code "39") (name "C7") (class "Default")
      (node (ref "H3") (pin "1") (pinfunction "1_1") (pintype "unspecified"))
      (node (ref "P2") (pin "11") (pinfunction "11_11") (pintype "unspecified"))
    )
    (net (code "40") (name "C8") (class "Default")
      (node (ref "H9") (pin "3") (pinfunction "3_3") (pintype "unspecified"))
      (node (ref "P2") (pin "12") (pinfunction "12_12") (pintype "unspecified"))
    )
    (net (code "41") (name "C9") (class "Default")
      (node (ref "H9") (pin "4") (pinfunction "4_4") (pintype "unspecified"))
      (node (ref "P2") (pin "13") (pinfunction "13_13") (pintype "unspecified"))
    )
    (net (code "42") (name "C10") (class "Default")
      (node (ref "H2") (pin "1") (pinfunction "1_1") (pintype "unspecified"))
      (node (ref "P2") (pin "14") (pinfunction "14_14") (pintype "unspecified"))
    )
    (net (code "43") (name "C11") (class "Default")
      (node (ref "H4") (pin "1") (pinfunction "1_1") (pintype "unspecified"))
      (node (ref "P2") (pin "15") (pinfunction "15_15") (pintype "unspecified"))
    )
    (net (code "44") (name "C12") (class "Default")
      (node (ref "P2") (pin "16") (pinfunction "16_16") (pintype "unspecified"))
    )
    (net (code "45") (name "C13") (class "Default")
      (node (ref "P2") (pin "17") (pinfunction "17_17") (pintype "unspecified"))
    )
    (net (code "46") (name "C14") (class "Default")
      (node (ref "P2") (pin "18") (pinfunction "18_18") (pintype "unspecified"))
    )
    (net (code "47") (name "C15") (class "Default")
      (node (ref "P2") (pin "19") (pinfunction "19_19") (pintype "unspecified"))
    )
    (net (code "48") (name "C16") (class "Default")
      (node (ref "H10") (pin "3") (pinfunction "3_3") (pintype "unspecified"))
      (node (ref "P2") (pin "20") (pinfunction "20_20") (pintype "unspecified"))
    )
    (net (code "49") (name "C17") (class "Default")
      (node (ref "H10") (pin "4") (pinfunction "4_4") (pintype "unspecified"))
      (node (ref "P2") (pin "21") (pinfunction "21_21") (pintype "unspecified"))
    )
    (net (code "50") (name "C18") (class "Default")
      (node (ref "J2") (pin "16") (pinfunction "16_16") (pintype "input"))
      (node (ref "P2") (pin "22") (pinfunction "22_22") (pintype "unspecified"))
    )
    (net (code "51") (name "C19") (class "Default")
      (node (ref "J2") (pin "12") (pinfunction "12_12") (pintype "input"))
      (node (ref "P2") (pin "23") (pinfunction "23_23") (pintype "unspecified"))
    )
    (net (code "52") (name "C20") (class "Default")
      (node (ref "P2") (pin "24") (pinfunction "24_24") (pintype "unspecified"))
      (node (ref "P5") (pin "6") (pinfunction "6_6") (pintype "input"))
    )
    (net (code "53") (name "C21") (class "Default")
      (node (ref "P2") (pin "25") (pinfunction "25_25") (pintype "unspecified"))
      (node (ref "P5") (pin "5") (pinfunction "5_5") (pintype "input"))
    )
    (net (code "54") (name "C22") (class "Default")
      (node (ref "P2") (pin "26") (pinfunction "26_26") (pintype "unspecified"))
      (node (ref "P5") (pin "4") (pinfunction "4_4") (pintype "input"))
    )
    (net (code "55") (name "C23") (class "Default")
      (node (ref "P2") (pin "27") (pinfunction "27_27") (pintype "unspecified"))
      (node (ref "P5") (pin "3") (pinfunction "3_3") (pintype "input"))
    )
    (net (code "56") (name "C24") (class "Default")
      (node (ref "H8") (pin "3") (pinfunction "3_3") (pintype "unspecified"))
      (node (ref "P2") (pin "28") (pinfunction "28_28") (pintype "unspecified"))
    )
    (net (code "57") (name "C25") (class "Default")
      (node (ref "H7") (pin "4") (pinfunction "4_4") (pintype "unspecified"))
      (node (ref "P2") (pin "29") (pinfunction "29_29") (pintype "unspecified"))
    )
    (net (code "58") (name "C26") (class "Default")
      (node (ref "P2") (pin "30") (pinfunction "30_30") (pintype "unspecified"))
      (node (ref "SW4") (pin "1") (pinfunction "1_1") (pintype "unspecified"))
    )
    (net (code "59") (name "C27") (class "Default")
      (node (ref "P2") (pin "31") (pinfunction "31_31") (pintype "unspecified"))
      (node (ref "SW3") (pin "1") (pinfunction "1_1") (pintype "unspecified"))
    )
    (net (code "60") (name "C28") (class "Default")
      (node (ref "J1") (pin "9") (pinfunction "9_9") (pintype "input"))
      (node (ref "P2") (pin "32") (pinfunction "32_32") (pintype "unspecified"))
    )
    (net (code "61") (name "C29") (class "Default")
      (node (ref "J1") (pin "11") (pinfunction "11_11") (pintype "input"))
      (node (ref "P2") (pin "33") (pinfunction "33_33") (pintype "unspecified"))
    )
    (net (code "62") (name "C30") (class "Default")
      (node (ref "P2") (pin "34") (pinfunction "34_34") (pintype "unspecified"))
    )
    (net (code "63") (name "C31") (class "Default")
      (node (ref "P2") (pin "36") (pinfunction "36_36") (pintype "unspecified"))
      (node (ref "SW2") (pin "1") (pinfunction "1_1") (pintype "unspecified"))
    )
    (net (code "64") (name "CR") (class "Default")
      (node (ref "D1") (pin "1") (pinfunction "C_1") (pintype "unspecified"))
      (node (ref "P1") (pin "9") (pinfunction "9_9") (pintype "unspecified"))
      (node (ref "R24") (pin "1") (pinfunction "1_1") (pintype "input"))
    )
    (net (code "65") (name "CR_OUT") (class "Default")
      (node (ref "C21") (pin "2") (pinfunction "2_2") (pintype "input"))
      (node (ref "D1") (pin "2") (pinfunction "A_2") (pintype "unspecified"))
      (node (ref "R24") (pin "2") (pinfunction "2_2") (pintype "input"))
      (node (ref "R31") (pin "1") (pinfunction "1_1") (pintype "input"))
      (node (ref "R32") (pin "1") (pinfunction "1_1") (pintype "input"))
      (node (ref "U3") (pin "3") (pinfunction "EN_3") (pintype "unspecified"))
      (node (ref "U4") (pin "3") (pinfunction "EN_3") (pintype "unspecified"))
    )
    (net (code "66") (name "D0") (class "Default")
      (node (ref "P1") (pin "14") (pinfunction "14_14") (pintype "unspecified"))
      (node (ref "R5") (pin "1") (pinfunction "1_1") (pintype "input"))
    )
    (net (code "67") (name "D1") (class "Default")
      (node (ref "P1") (pin "13") (pinfunction "13_13") (pintype "unspecified"))
      (node (ref "R7") (pin "2") (pinfunction "2_2") (pintype "input"))
    )
    (net (code "68") (name "D2") (class "Default")
      (node (ref "P1") (pin "12") (pinfunction "12_12") (pintype "unspecified"))
      (node (ref "R6") (pin "1") (pinfunction "1_1") (pintype "input"))
    )
    (net (code "69") (name "D3") (class "Default")
      (node (ref "P1") (pin "11") (pinfunction "11_11") (pintype "unspecified"))
      (node (ref "R8") (pin "2") (pinfunction "2_2") (pintype "input"))
    )
    (net (code "70") (name "D4") (class "Default")
      (node (ref "F1") (pin "1") (pinfunction "1_1") (pintype "unspecified"))
      (node (ref "P1") (pin "10") (pinfunction "10_10") (pintype "unspecified"))
    )
    (net (code "71") (name "D12") (class "Default")
      (node (ref "P1") (pin "15") (pinfunction "15_15") (pintype "unspecified"))
      (node (ref "R1") (pin "1") (pinfunction "1_1") (pintype "input"))
    )
    (net (code "72") (name "D13") (class "Default")
      (node (ref "P1") (pin "16") (pinfunction "16_16") (pintype "unspecified"))
      (node (ref "R3") (pin "2") (pinfunction "2_2") (pintype "input"))
    )
    (net (code "73") (name "D14") (class "Default")
      (node (ref "P1") (pin "17") (pinfunction "17_17") (pintype "unspecified"))
      (node (ref "R2") (pin "1") (pinfunction "1_1") (pintype "input"))
    )
    (net (code "74") (name "D15") (class "Default")
      (node (ref "P1") (pin "18") (pinfunction "18_18") (pintype "unspecified"))
      (node (ref "R4") (pin "2") (pinfunction "2_2") (pintype "input"))
    )
    (net (code "75") (name "D16") (class "Default")
      (node (ref "P1") (pin "19") (pinfunction "19_19") (pintype "unspecified"))
      (node (ref "U12") (pin "1") (pinfunction "1_1") (pintype "unspecified"))
    )
    (net (code "76") (name "D17") (class "Default")
      (node (ref "P1") (pin "20") (pinfunction "20_20") (pintype "unspecified"))
      (node (ref "U12") (pin "3") (pinfunction "3_3") (pintype "unspecified"))
    )
    (net (code "77") (name "D26") (class "Default")
      (node (ref "P2") (pin "2") (pinfunction "2_2") (pintype "unspecified"))
      (node (ref "U12") (pin "4") (pinfunction "4_4") (pintype "unspecified"))
    )
    (net (code "78") (name "D27") (class "Default")
      (node (ref "F1") (pin "2") (pinfunction "2_2") (pintype "unspecified"))
      (node (ref "P2") (pin "3") (pinfunction "3_3") (pintype "unspecified"))
    )
    (net (code "79") (name "FC3V3") (class "Default")
      (node (ref "C18") (pin "2") (pinfunction "2_2") (pintype "input"))
      (node (ref "C20") (pin "1") (pinfunction "1_1") (pintype "input"))
      (node (ref "J1") (pin "1") (pinfunction "1_1") (pintype "input"))
      (node (ref "R28") (pin "2") (pinfunction "2_2") (pintype "input"))
      (node (ref "U4") (pin "5") (pinfunction "VOUT_5") (pintype "unspecified"))
    )
    (net (code "80") (name "GND") (class "Default")
      (node (ref "3V3") (pin "2") (pinfunction "-_2") (pintype "unspecified"))
      (node (ref "5V") (pin "2") (pinfunction "-_2") (pintype "unspecified"))
      (node (ref "C1") (pin "2") (pinfunction "2_2") (pintype "input"))
      (node (ref "C10") (pin "1") (pinfunction "1_1") (pintype "input"))
      (node (ref "C11") (pin "1") (pinfunction "1_1") (pintype "input"))
      (node (ref "C12") (pin "1") (pinfunction "1_1") (pintype "input"))
      (node (ref "C13") (pin "2") (pinfunction "2_2") (pintype "input"))
      (node (ref "C14") (pin "2") (pinfunction "2_2") (pintype "input"))
      (node (ref "C15") (pin "2") (pinfunction "2_2") (pintype "input"))
      (node (ref "C16") (pin "1") (pinfunction "1_1") (pintype "input"))
      (node (ref "C17") (pin "1") (pinfunction "1_1") (pintype "input"))
      (node (ref "C18") (pin "1") (pinfunction "1_1") (pintype "input"))
      (node (ref "C19") (pin "1") (pinfunction "1_1") (pintype "input"))
      (node (ref "C2") (pin "1") (pinfunction "1_1") (pintype "input"))
      (node (ref "C20") (pin "2") (pinfunction "2_2") (pintype "input"))
      (node (ref "C21") (pin "1") (pinfunction "1_1") (pintype "input"))
      (node (ref "C23") (pin "2") (pinfunction "2_2") (pintype "input"))
      (node (ref "C3") (pin "1") (pinfunction "1_1") (pintype "input"))
      (node (ref "C5") (pin "1") (pinfunction "1_1") (pintype "input"))
      (node (ref "C6") (pin "2") (pinfunction "2_2") (pintype "input"))
      (node (ref "C7") (pin "1") (pinfunction "1_1") (pintype "input"))
      (node (ref "C8") (pin "1") (pinfunction "1_1") (pintype "input"))
      (node (ref "C9") (pin "2") (pinfunction "2_2") (pintype "input"))
      (node (ref "D2") (pin "2") (pinfunction "A_2") (pintype "unspecified"))
      (node (ref "F1") (pin "3") (pinfunction "3_3") (pintype "unspecified"))
      (node (ref "F1") (pin "4") (pinfunction "4_4") (pintype "unspecified"))
      (node (ref "FC") (pin "2") (pinfunction "-_2") (pintype "unspecified"))
      (node (ref "H1") (pin "3") (pinfunction "3_3") (pintype "unspecified"))
      (node (ref "H10") (pin "2") (pinfunction "2_2") (pintype "unspecified"))
      (node (ref "H11") (pin "2") (pinfunction "2_2") (pintype "unspecified"))
      (node (ref "H12") (pin "3") (pinfunction "3_3") (pintype "unspecified"))
      (node (ref "H12") (pin "4") (pinfunction "4_4") (pintype "unspecified"))
      (node (ref "H13") (pin "3") (pinfunction "3_3") (pintype "unspecified"))
      (node (ref "H13") (pin "4") (pinfunction "4_4") (pintype "unspecified"))
      (node (ref "H14") (pin "6") (pinfunction "6_6") (pintype "unspecified"))
      (node (ref "H14") (pin "8") (pinfunction "8_8") (pintype "unspecified"))
      (node (ref "H2") (pin "3") (pinfunction "3_3") (pintype "unspecified"))
      (node (ref "H3") (pin "3") (pinfunction "3_3") (pintype "unspecified"))
      (node (ref "H4") (pin "3") (pinfunction "3_3") (pintype "unspecified"))
      (node (ref "H5") (pin "1") (pinfunction "1_1") (pintype "unspecified"))
      (node (ref "H6") (pin "6") (pinfunction "6_6") (pintype "unspecified"))
      (node (ref "H7") (pin "1") (pinfunction "1_1") (pintype "unspecified"))
      (node (ref "H8") (pin "6") (pinfunction "6_6") (pintype "unspecified"))
      (node (ref "H9") (pin "2") (pinfunction "2_2") (pintype "unspecified"))
      (node (ref "J1") (pin "13") (pinfunction "13_13") (pintype "input"))
      (node (ref "J1") (pin "3") (pinfunction "3_3") (pintype "input"))
      (node (ref "J2") (pin "2") (pinfunction "2_2") (pintype "input"))
      (node (ref "P1") (pin "1") (pinfunction "1_1") (pintype "unspecified"))
      (node (ref "P1") (pin "2") (pinfunction "2_2") (pintype "unspecified"))
      (node (ref "P2") (pin "1") (pinfunction "1_1") (pintype "unspecified"))
      (node (ref "P5") (pin "2") (pinfunction "2_2") (pintype "input"))
      (node (ref "Q1") (pin "2") (pinfunction "E_2") (pintype "unspecified"))
      (node (ref "Q2") (pin "3") (pinfunction "S_3") (pintype "unspecified"))
      (node (ref "Q2") (pin "4") (pinfunction "D_4") (pintype "unspecified"))
      (node (ref "R11") (pin "2") (pinfunction "2_2") (pintype "input"))
      (node (ref "R14") (pin "2") (pinfunction "2_2") (pintype "input"))
      (node (ref "R16") (pin "2") (pinfunction "2_2") (pintype "input"))
      (node (ref "R19") (pin "2") (pinfunction "2_2") (pintype "input"))
      (node (ref "R21") (pin "2") (pinfunction "2_2") (pintype "input"))
      (node (ref "R22") (pin "2") (pinfunction "2_2") (pintype "input"))
      (node (ref "R30") (pin "1") (pinfunction "1_1") (pintype "input"))
      (node (ref "SE") (pin "2") (pinfunction "-_2") (pintype "unspecified"))
      (node (ref "SW2") (pin "2") (pinfunction "2_2") (pintype "unspecified"))
      (node (ref "SW3") (pin "2") (pinfunction "2_2") (pintype "unspecified"))
      (node (ref "SW4") (pin "2") (pinfunction "2_2") (pintype "unspecified"))
      (node (ref "SW5") (pin "2") (pinfunction "2_2") (pintype "unspecified"))
      (node (ref "U1") (pin "7") (pinfunction "GND_7") (pintype "unspecified"))
      (node (ref "U1") (pin "9") (pinfunction "EP_9") (pintype "unspecified"))
      (node (ref "U12") (pin "5") (pinfunction "5_5") (pintype "unspecified"))
      (node (ref "U12") (pin "6") (pinfunction "6_6") (pintype "unspecified"))
      (node (ref "U2") (pin "7") (pinfunction "GND_7") (pintype "unspecified"))
      (node (ref "U2") (pin "9") (pinfunction "EP_9") (pintype "unspecified"))
      (node (ref "U3") (pin "2") (pinfunction "GND_2") (pintype "unspecified"))
      (node (ref "U4") (pin "2") (pinfunction "GND_2") (pintype "unspecified"))
      (node (ref "U5") (pin "1") (pinfunction "-_1") (pintype "unspecified"))
      (node (ref "U7") (pin "1") (pinfunction "-_1") (pintype "unspecified"))
      (node (ref "U8") (pin "1") (pinfunction "-_1") (pintype "unspecified"))
    )
    (net (code "81") (name "Net-(3V3-+)") (class "Default")
      (node (ref "3V3") (pin "1") (pinfunction "+_1") (pintype "unspecified"))
      (node (ref "R27") (pin "1") (pinfunction "1_1") (pintype "input"))
    )
    (net (code "82") (name "Net-(5V-+)") (class "Default")
      (node (ref "5V") (pin "1") (pinfunction "+_1") (pintype "unspecified"))
      (node (ref "R26") (pin "1") (pinfunction "1_1") (pintype "input"))
    )
    (net (code "83") (name "Net-(BUZZER1-+)") (class "Default")
      (node (ref "BUZZER1") (pin "1") (pinfunction "+_1") (pintype "unspecified"))
      (node (ref "R9") (pin "2") (pinfunction "2_2") (pintype "input"))
    )
    (net (code "84") (name "Net-(C7-Pad2)") (class "Default")
      (node (ref "C7") (pin "2") (pinfunction "2_2") (pintype "input"))
      (node (ref "R15") (pin "1") (pinfunction "1_1") (pintype "input"))
    )
    (net (code "85") (name "Net-(C8-Pad2)") (class "Default")
      (node (ref "C8") (pin "2") (pinfunction "2_2") (pintype "input"))
      (node (ref "R20") (pin "1") (pinfunction "1_1") (pintype "input"))
    )
    (net (code "86") (name "Net-(FC-+)") (class "Default")
      (node (ref "FC") (pin "1") (pinfunction "+_1") (pintype "unspecified"))
      (node (ref "R28") (pin "1") (pinfunction "1_1") (pintype "input"))
    )
    (net (code "87") (name "Net-(H12-Pad1)") (class "Default")
      (node (ref "H12") (pin "1") (pinfunction "1_1") (pintype "unspecified"))
      (node (ref "R1") (pin "2") (pinfunction "2_2") (pintype "input"))
    )
    (net (code "88") (name "Net-(H12-Pad2)") (class "Default")
      (node (ref "H12") (pin "2") (pinfunction "2_2") (pintype "unspecified"))
      (node (ref "R3") (pin "1") (pinfunction "1_1") (pintype "input"))
    )
    (net (code "89") (name "Net-(H12-Pad5)") (class "Default")
      (node (ref "H12") (pin "5") (pinfunction "5_5") (pintype "unspecified"))
      (node (ref "R2") (pin "2") (pinfunction "2_2") (pintype "input"))
    )
    (net (code "90") (name "Net-(H12-Pad6)") (class "Default")
      (node (ref "H12") (pin "6") (pinfunction "6_6") (pintype "unspecified"))
      (node (ref "R4") (pin "1") (pinfunction "1_1") (pintype "input"))
    )
    (net (code "91") (name "Net-(H13-Pad1)") (class "Default")
      (node (ref "H13") (pin "1") (pinfunction "1_1") (pintype "unspecified"))
      (node (ref "R5") (pin "2") (pinfunction "2_2") (pintype "input"))
    )
    (net (code "92") (name "Net-(H13-Pad2)") (class "Default")
      (node (ref "H13") (pin "2") (pinfunction "2_2") (pintype "unspecified"))
      (node (ref "R7") (pin "1") (pinfunction "1_1") (pintype "input"))
    )
    (net (code "93") (name "Net-(H13-Pad5)") (class "Default")
      (node (ref "H13") (pin "5") (pinfunction "5_5") (pintype "unspecified"))
      (node (ref "R6") (pin "2") (pinfunction "2_2") (pintype "input"))
    )
    (net (code "94") (name "Net-(H13-Pad6)") (class "Default")
      (node (ref "H13") (pin "6") (pinfunction "6_6") (pintype "unspecified"))
      (node (ref "R8") (pin "1") (pinfunction "1_1") (pintype "input"))
    )
    (net (code "95") (name "Net-(J1-Pad7)") (class "Default")
      (node (ref "J1") (pin "7") (pinfunction "7_7") (pintype "input"))
      (node (ref "R30") (pin "2") (pinfunction "2_2") (pintype "input"))
    )
    (net (code "96") (name "Net-(Q1-B)") (class "Default")
      (node (ref "Q1") (pin "1") (pinfunction "B_1") (pintype "unspecified"))
      (node (ref "R10") (pin "2") (pinfunction "2_2") (pintype "input"))
    )
    (net (code "97") (name "Net-(Q1-C)") (class "Default")
      (node (ref "BUZZER1") (pin "2") (pinfunction "2_2") (pintype "unspecified"))
      (node (ref "Q1") (pin "3") (pinfunction "C_3") (pintype "unspecified"))
    )
    (net (code "98") (name "Net-(Q2-G)") (class "Default")
      (node (ref "Q2") (pin "1") (pinfunction "G_1") (pintype "unspecified"))
      (node (ref "R23") (pin "2") (pinfunction "2_2") (pintype "input"))
    )
    (net (code "99") (name "Net-(R12-Pad2)") (class "Default")
      (node (ref "R12") (pin "2") (pinfunction "2_2") (pintype "input"))
      (node (ref "R13") (pin "1") (pinfunction "1_1") (pintype "unspecified"))
      (node (ref "R13") (pin "2") (pinfunction "2_2") (pintype "unspecified"))
    )
    (net (code "100") (name "Net-(R17-Pad2)") (class "Default")
      (node (ref "R17") (pin "2") (pinfunction "2_2") (pintype "input"))
      (node (ref "R18") (pin "1") (pinfunction "1_1") (pintype "input"))
    )
    (net (code "101") (name "Net-(SE-+)") (class "Default")
      (node (ref "R25") (pin "1") (pinfunction "1_1") (pintype "input"))
      (node (ref "SE") (pin "1") (pinfunction "+_1") (pintype "unspecified"))
    )
    (net (code "102") (name "Net-(U1-BOOT)") (class "Default")
      (node (ref "C4") (pin "2") (pinfunction "2_2") (pintype "input"))
      (node (ref "U1") (pin "1") (pinfunction "BOOT_1") (pintype "unspecified"))
    )
    (net (code "103") (name "Net-(U1-COMP)") (class "Default")
      (node (ref "R15") (pin "2") (pinfunction "2_2") (pintype "input"))
      (node (ref "U1") (pin "6") (pinfunction "COMP_6") (pintype "unspecified"))
    )
    (net (code "104") (name "Net-(U1-FB)") (class "Default")
      (node (ref "R13") (pin "3") (pinfunction "3_3") (pintype "unspecified"))
      (node (ref "R14") (pin "1") (pinfunction "1_1") (pintype "input"))
      (node (ref "U1") (pin "5") (pinfunction "FB_5") (pintype "unspecified"))
    )
    (net (code "105") (name "Net-(U1-RT{slash}CLK)") (class "Default")
      (node (ref "R16") (pin "1") (pinfunction "1_1") (pintype "input"))
      (node (ref "U1") (pin "4") (pinfunction "RT/CLK_4") (pintype "unspecified"))
    )
    (net (code "106") (name "Net-(U1-SW)") (class "Default")
      (node (ref "C4") (pin "1") (pinfunction "1_1") (pintype "input"))
      (node (ref "L1") (pin "1") (pinfunction "1_1") (pintype "unspecified"))
      (node (ref "U1") (pin "8") (pinfunction "SW_8") (pintype "unspecified"))
    )
    (net (code "107") (name "Net-(U2-BOOT)") (class "Default")
      (node (ref "C22") (pin "2") (pinfunction "2_2") (pintype "input"))
      (node (ref "U2") (pin "1") (pinfunction "BOOT_1") (pintype "unspecified"))
    )
    (net (code "108") (name "Net-(U2-COMP)") (class "Default")
      (node (ref "R20") (pin "2") (pinfunction "2_2") (pintype "input"))
      (node (ref "U2") (pin "6") (pinfunction "COMP_6") (pintype "unspecified"))
    )
    (net (code "109") (name "Net-(U2-FB)") (class "Default")
      (node (ref "R18") (pin "2") (pinfunction "2_2") (pintype "input"))
      (node (ref "R19") (pin "1") (pinfunction "1_1") (pintype "input"))
      (node (ref "U2") (pin "5") (pinfunction "FB_5") (pintype "unspecified"))
    )
    (net (code "110") (name "Net-(U2-RT{slash}CLK)") (class "Default")
      (node (ref "R21") (pin "1") (pinfunction "1_1") (pintype "input"))
      (node (ref "U2") (pin "4") (pinfunction "RT/CLK_4") (pintype "unspecified"))
    )
    (net (code "111") (name "Net-(U2-SW)") (class "Default")
      (node (ref "C22") (pin "1") (pinfunction "1_1") (pintype "input"))
      (node (ref "L2") (pin "1") (pinfunction "1_1") (pintype "unspecified"))
      (node (ref "U2") (pin "8") (pinfunction "SW_8") (pintype "unspecified"))
    )
    (net (code "112") (name "OF") (class "Default")
      (node (ref "P1") (pin "7") (pinfunction "7_7") (pintype "unspecified"))
    )
    (net (code "113") (name "VCC") (class "Default")
      (node (ref "C1") (pin "1") (pinfunction "1_1") (pintype "input"))
      (node (ref "C11") (pin "2") (pinfunction "2_2") (pintype "input"))
      (node (ref "C12") (pin "2") (pinfunction "2_2") (pintype "input"))
      (node (ref "C13") (pin "1") (pinfunction "1_1") (pintype "input"))
      (node (ref "C2") (pin "2") (pinfunction "2_2") (pintype "input"))
      (node (ref "C3") (pin "2") (pinfunction "2_2") (pintype "input"))
      (node (ref "D2") (pin "1") (pinfunction "K_1") (pintype "unspecified"))
      (node (ref "R22") (pin "1") (pinfunction "1_1") (pintype "input"))
      (node (ref "R23") (pin "1") (pinfunction "1_1") (pintype "input"))
      (node (ref "SW1") (pin "1") (pinfunction "1_1") (pintype "unspecified"))
      (node (ref "U1") (pin "2") (pinfunction "VIN_2") (pintype "unspecified"))
      (node (ref "U1") (pin "3") (pinfunction "EN_3") (pintype "unspecified"))
      (node (ref "U2") (pin "2") (pinfunction "VIN_2") (pintype "unspecified"))
      (node (ref "U2") (pin "3") (pinfunction "EN_3") (pintype "unspecified"))
      (node (ref "U7") (pin "2") (pinfunction "+_2") (pintype "unspecified"))
      (node (ref "U8") (pin "2") (pinfunction "+_2") (pintype "unspecified"))
    )
    (net (code "114") (name "VCCBAT") (class "Default")
      (node (ref "SW1") (pin "2") (pinfunction "2_2") (pintype "unspecified"))
      (node (ref "U5") (pin "2") (pinfunction "+_2") (pintype "unspecified"))
    )
    (net (code "115") (name "VCCSERVO") (class "Default")
      (node (ref "C5") (pin "2") (pinfunction "2_2") (pintype "input"))
      (node (ref "C6") (pin "1") (pinfunction "1_1") (pintype "input"))
      (node (ref "H1") (pin "2") (pinfunction "2_2") (pintype "unspecified"))
      (node (ref "H2") (pin "2") (pinfunction "2_2") (pintype "unspecified"))
      (node (ref "H3") (pin "2") (pinfunction "2_2") (pintype "unspecified"))
      (node (ref "H4") (pin "2") (pinfunction "2_2") (pintype "unspecified"))
      (node (ref "L1") (pin "2") (pinfunction "2_2") (pintype "unspecified"))
      (node (ref "R12") (pin "1") (pinfunction "1_1") (pintype "input"))
      (node (ref "R25") (pin "2") (pinfunction "2_2") (pintype "input"))
    )
    (net (code "116") (name "WU") (class "Default")
      (node (ref "P1") (pin "8") (pinfunction "8_8") (pintype "unspecified"))
    )
    (net (code "117") (name "unconnected-(H5-Pad5)") (class "Default")
      (node (ref "H5") (pin "5") (pinfunction "5_5") (pintype "unspecified+no_connect"))
    )
    (net (code "118") (name "unconnected-(H5-Pad6)") (class "Default")
      (node (ref "H5") (pin "6") (pinfunction "6_6") (pintype "unspecified+no_connect"))
    )
    (net (code "119") (name "unconnected-(H6-Pad1)") (class "Default")
      (node (ref "H6") (pin "1") (pinfunction "1_1") (pintype "unspecified+no_connect"))
    )
    (net (code "120") (name "unconnected-(H6-Pad2)") (class "Default")
      (node (ref "H6") (pin "2") (pinfunction "2_2") (pintype "unspecified+no_connect"))
    )
    (net (code "121") (name "unconnected-(H7-Pad5)") (class "Default")
      (node (ref "H7") (pin "5") (pinfunction "5_5") (pintype "unspecified+no_connect"))
    )
    (net (code "122") (name "unconnected-(H7-Pad6)") (class "Default")
      (node (ref "H7") (pin "6") (pinfunction "6_6") (pintype "unspecified+no_connect"))
    )
    (net (code "123") (name "unconnected-(H8-Pad1)") (class "Default")
      (node (ref "H8") (pin "1") (pinfunction "1_1") (pintype "unspecified+no_connect"))
    )
    (net (code "124") (name "unconnected-(H8-Pad2)") (class "Default")
      (node (ref "H8") (pin "2") (pinfunction "2_2") (pintype "unspecified+no_connect"))
    )
    (net (code "125") (name "unconnected-(J2-Pad1)") (class "Default")
      (node (ref "J2") (pin "1") (pinfunction "1_1") (pintype "input+no_connect"))
    )
    (net (code "126") (name "unconnected-(J2-Pad3)") (class "Default")
      (node (ref "J2") (pin "3") (pinfunction "3_3") (pintype "input+no_connect"))
    )
    (net (code "127") (name "unconnected-(J2-Pad5)") (class "Default")
      (node (ref "J2") (pin "5") (pinfunction "5_5") (pintype "input+no_connect"))
    )
    (net (code "128") (name "unconnected-(J2-Pad7)") (class "Default")
      (node (ref "J2") (pin "7") (pinfunction "7_7") (pintype "input+no_connect"))
    )
    (net (code "129") (name "unconnected-(J2-Pad9)") (class "Default")
      (node (ref "J2") (pin "9") (pinfunction "9_9") (pintype "input+no_connect"))
    )
    (net (code "130") (name "unconnected-(J2-Pad11)") (class "Default")
      (node (ref "J2") (pin "11") (pinfunction "11_11") (pintype "input+no_connect"))
    )
    (net (code "131") (name "unconnected-(J2-Pad13)") (class "Default")
      (node (ref "J2") (pin "13") (pinfunction "13_13") (pintype "input+no_connect"))
    )
    (net (code "132") (name "unconnected-(J2-Pad15)") (class "Default")
      (node (ref "J2") (pin "15") (pinfunction "15_15") (pintype "input+no_connect"))
    )
    (net (code "133") (name "unconnected-(P5-Pad7)") (class "Default")
      (node (ref "P5") (pin "7") (pinfunction "7_7") (pintype "input+no_connect"))
    )
    (net (code "134") (name "unconnected-(P5-Pad8)") (class "Default")
      (node (ref "P5") (pin "8") (pinfunction "8_8") (pintype "input+no_connect"))
    )
    (net (code "135") (name "unconnected-(SW1-Pad3)") (class "Default")
      (node (ref "SW1") (pin "3") (pinfunction "3_3") (pintype "unspecified+no_connect"))
    )
    (net (code "136") (name "unconnected-(U3-NC-Pad4)") (class "Default")
      (node (ref "U3") (pin "4") (pinfunction "NC_4") (pintype "unspecified+no_connect"))
    )
    (net (code "137") (name "unconnected-(U4-NC-Pad4)") (class "Default")
      (node (ref "U4") (pin "4") (pinfunction "NC_4") (pintype "unspecified+no_connect"))
    )
    (net (code "138") (name "unconnected-(U12-Pad2)") (class "Default")
      (node (ref "U12") (pin "2") (pinfunction "2_2") (pintype "unspecified+no_connect"))
    )
    (net (code "139") (name "unconnected-(U12-Pad8)") (class "Default")
      (node (ref "U12") (pin "8") (pinfunction "8_8") (pintype "unspecified+no_connect"))
    )
  )
)
